# TSOC_CYBLE022.net
KiCad netlist of a schematic drawn in EAGLE
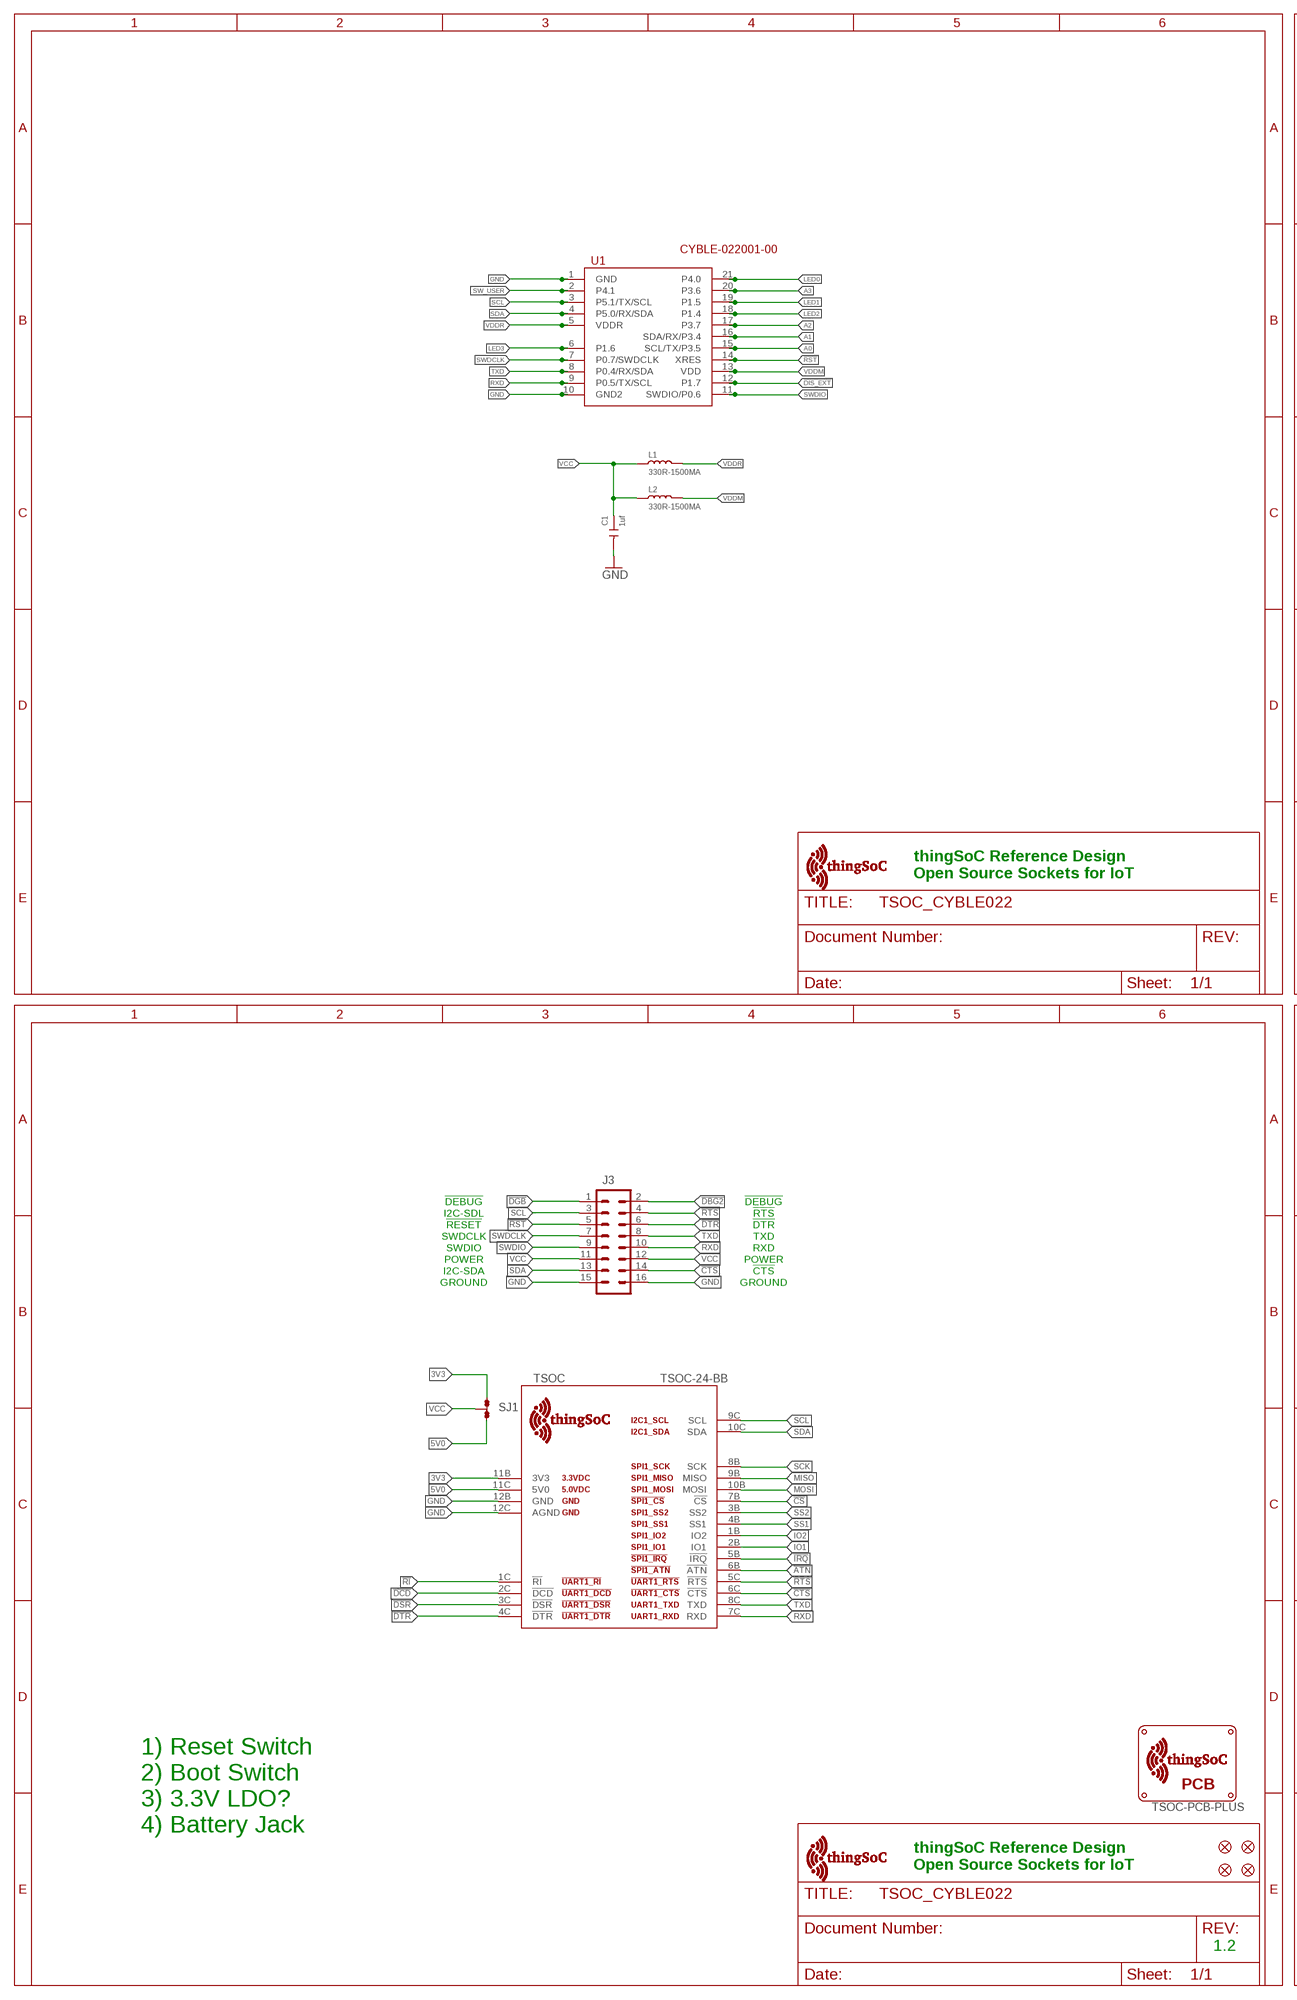
[diagram p0: schematic, sheet 1, part 1 of 2]
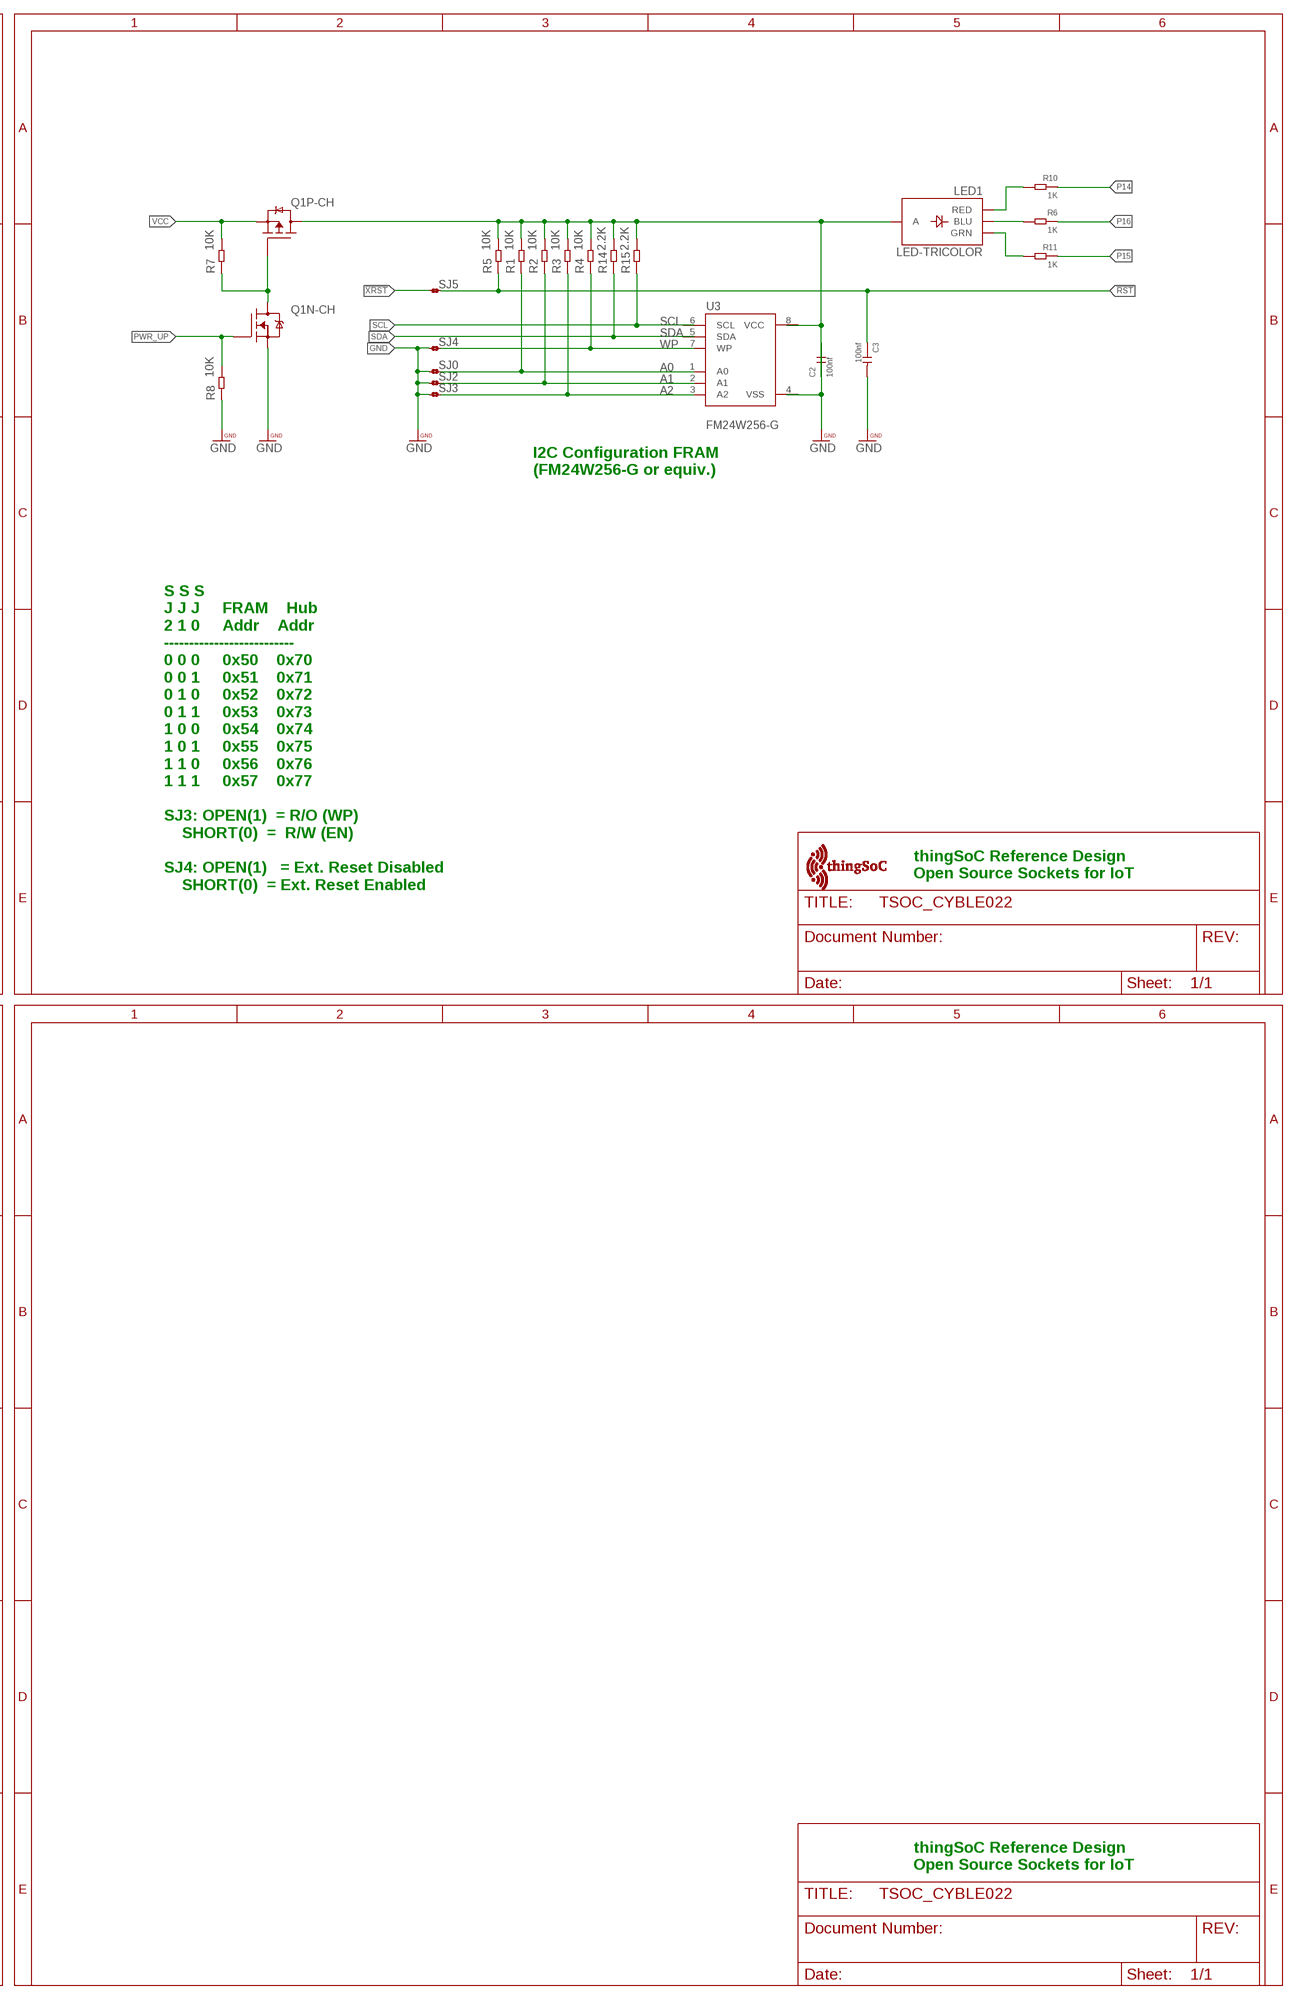
[diagram p1: schematic, sheet 1, part 2 of 2]

(export (version "E")
  (design (tool "Eeschema 10.0.6"))
  (components
    (comp (ref "$$U$4")
      (value "TSOC-LOGO-SMALL")
      (footprint "eagle-import:TSOC-LOGO-SML")
      (libsource (lib "eagle-import") (part "TSOC-LOGO-SMALL"))
    )
    (comp (ref "C1")
      (value "1uf")
      (footprint "eagle-import:C0603")
      (fields (field (name "MPN") "CC0603KRX7R8BB105"))
      (libsource (lib "eagle-import") (part "CERAMIC-1UF-25V-10%-X7R(0603)"))
    )
    (comp (ref "C2")
      (value "100nf")
      (footprint "eagle-import:C0603")
      (fields (field (name "MPN") "CC0603KRX7R9BB104"))
      (libsource (lib "eagle-import") (part "CERAMIC-100NF-50V-10%-X7R(0603)"))
    )
    (comp (ref "C3")
      (value "100nf")
      (footprint "eagle-import:C0603")
      (fields (field (name "MPN") "CC0603KRX7R9BB104"))
      (libsource (lib "eagle-import") (part "CERAMIC-100NF-50V-10%-X7R(0603)"))
    )
    (comp (ref "FID1")
      (value "FIDUCIALUFIDUCIAL")
      (footprint "eagle-import:MICRO-FIDUCIAL")
      (libsource (lib "eagle-import") (part "FIDUCIALUFIDUCIAL"))
    )
    (comp (ref "FID2")
      (value "FIDUCIALUFIDUCIAL")
      (footprint "eagle-import:MICRO-FIDUCIAL")
      (libsource (lib "eagle-import") (part "FIDUCIALUFIDUCIAL"))
    )
    (comp (ref "FID3")
      (value "FIDUCIALUFIDUCIAL")
      (footprint "eagle-import:MICRO-FIDUCIAL")
      (libsource (lib "eagle-import") (part "FIDUCIALUFIDUCIAL"))
    )
    (comp (ref "FID4")
      (value "FIDUCIALUFIDUCIAL")
      (footprint "eagle-import:MICRO-FIDUCIAL")
      (libsource (lib "eagle-import") (part "FIDUCIALUFIDUCIAL"))
    )
    (comp (ref "J3")
      (value "M08X2")
      (footprint "eagle-import:2X8")
      (libsource (lib "eagle-import") (part "M08X2"))
    )
    (comp (ref "L1")
      (value "330R-1500MA")
      (footprint "eagle-import:L0805")
      (fields (field (name "MPN") "BLM21PG331SN1D"))
      (libsource (lib "eagle-import") (part "SMD-FERRITE-BEAD-330R-1500MA(0805)'0805'"))
    )
    (comp (ref "L2")
      (value "330R-1500MA")
      (footprint "eagle-import:L0805")
      (fields (field (name "MPN") "BLM21PG331SN1D"))
      (libsource (lib "eagle-import") (part "SMD-FERRITE-BEAD-330R-1500MA(0805)'0805'"))
    )
    (comp (ref "LED1")
      (value "LED-TRICOLOR")
      (footprint "eagle-import:LED-TRICOLOR-SMD")
      (libsource (lib "eagle-import") (part "LED-TRICOLOR"))
    )
    (comp (ref "Q1")
      (value "FDC6420C")
      (footprint "eagle-import:SOT95P280X110-6N")
      (libsource (lib "eagle-import") (part "FDC6420C"))
    )
    (comp (ref "R1")
      (value "10K")
      (footprint "eagle-import:R0603")
      (fields (field (name "MPN") "RC0603FR-0710KL"))
      (libsource (lib "eagle-import") (part "SMD-RES-10K-1%-1/10W(0603)"))
    )
    (comp (ref "R2")
      (value "10K")
      (footprint "eagle-import:R0603")
      (fields (field (name "MPN") "RC0603FR-0710KL"))
      (libsource (lib "eagle-import") (part "SMD-RES-10K-1%-1/10W(0603)"))
    )
    (comp (ref "R3")
      (value "10K")
      (footprint "eagle-import:R0603")
      (fields (field (name "MPN") "RC0603FR-0710KL"))
      (libsource (lib "eagle-import") (part "SMD-RES-10K-1%-1/10W(0603)"))
    )
    (comp (ref "R4")
      (value "10K")
      (footprint "eagle-import:R0603")
      (fields (field (name "MPN") "RC0603FR-0710KL"))
      (libsource (lib "eagle-import") (part "SMD-RES-10K-1%-1/10W(0603)"))
    )
    (comp (ref "R5")
      (value "10K")
      (footprint "eagle-import:R0603")
      (fields (field (name "MPN") "RC0603FR-0710KL"))
      (libsource (lib "eagle-import") (part "SMD-RES-10K-1%-1/10W(0603)"))
    )
    (comp (ref "R6")
      (value "1K")
      (footprint "eagle-import:R0603")
      (fields (field (name "MPN") "RC0603FR-071KL"))
      (libsource (lib "eagle-import") (part "SMD-RES-1K-1%-1/10W(0603)"))
    )
    (comp (ref "R7")
      (value "10K")
      (footprint "eagle-import:R0603")
      (fields (field (name "MPN") "RC0603FR-0710KL"))
      (libsource (lib "eagle-import") (part "SMD-RES-10K-1%-1/10W(0603)"))
    )
    (comp (ref "R8")
      (value "10K")
      (footprint "eagle-import:R0603")
      (fields (field (name "MPN") "RC0603FR-0710KL"))
      (libsource (lib "eagle-import") (part "SMD-RES-10K-1%-1/10W(0603)"))
    )
    (comp (ref "R10")
      (value "1K")
      (footprint "eagle-import:R0603")
      (fields (field (name "MPN") "RC0603FR-071KL"))
      (libsource (lib "eagle-import") (part "SMD-RES-1K-1%-1/10W(0603)"))
    )
    (comp (ref "R11")
      (value "1K")
      (footprint "eagle-import:R0603")
      (fields (field (name "MPN") "RC0603FR-071KL"))
      (libsource (lib "eagle-import") (part "SMD-RES-1K-1%-1/10W(0603)"))
    )
    (comp (ref "R14")
      (value "2.2K")
      (footprint "eagle-import:R0603")
      (fields (field (name "MPN") "RC0603JR-072K2L"))
      (libsource (lib "eagle-import") (part "SMD-RES-2.2K-5%-1/10W(0603)"))
    )
    (comp (ref "R15")
      (value "2.2K")
      (footprint "eagle-import:R0603")
      (fields (field (name "MPN") "RC0603JR-072K2L"))
      (libsource (lib "eagle-import") (part "SMD-RES-2.2K-5%-1/10W(0603)"))
    )
    (comp (ref "SJ0")
      (value "JMP-2-NO")
      (footprint "eagle-import:JMP-2-NO")
      (libsource (lib "eagle-import") (part "JMP-2-NO"))
    )
    (comp (ref "SJ1")
      (value "JMP-3-NC")
      (footprint "eagle-import:JMP-3-NC")
      (libsource (lib "eagle-import") (part "JMP-3-NC"))
    )
    (comp (ref "SJ2")
      (value "JMP-2-NO")
      (footprint "eagle-import:JMP-2-NO")
      (libsource (lib "eagle-import") (part "JMP-2-NO"))
    )
    (comp (ref "SJ3")
      (value "JMP-2-NO")
      (footprint "eagle-import:JMP-2-NO")
      (libsource (lib "eagle-import") (part "JMP-2-NO"))
    )
    (comp (ref "SJ4")
      (value "JMP-2-NO")
      (footprint "eagle-import:JMP-2-NO")
      (libsource (lib "eagle-import") (part "JMP-2-NO"))
    )
    (comp (ref "SJ5")
      (value "JMP-2-NO")
      (footprint "eagle-import:JMP-2-NO")
      (libsource (lib "eagle-import") (part "JMP-2-NO"))
    )
    (comp (ref "TSOC")
      (value "TSOC-24-BB")
      (footprint "eagle-import:TSOC-BB-S24")
      (libsource (lib "eagle-import") (part "TSOC-24-BB"))
    )
    (comp (ref "U$1")
      (value "TSOC-PCB-PLUS")
      (footprint "eagle-import:TSOC-BB-BRD-PLUS-DIM")
      (libsource (lib "eagle-import") (part "TSOC-PCB-PLUS"))
    )
    (comp (ref "U$100")
      (value "TSOC-LOGO-SMALL")
      (footprint "eagle-import:TSOC-LOGO-SML")
      (libsource (lib "eagle-import") (part "TSOC-LOGO-SMALL"))
    )
    (comp (ref "U$101")
      (value "TSOC-LOGO-LRG")
      (footprint "eagle-import:TSOC-LOGO-LRG")
      (libsource (lib "eagle-import") (part "TSOC-LOGO-LRG"))
    )
    (comp (ref "U1")
      (value "CYBLE-022001-00")
      (footprint "eagle-import:PROC-BLE-10MM-21")
      (libsource (lib "eagle-import") (part "CYBLE-022001-00"))
    )
    (comp (ref "U3")
      (value "FM24W256-G")
      (footprint "eagle-import:SO08")
      (libsource (lib "eagle-import") (part "FM24W256-G"))
    )
  )
  (nets
    (net (code "1") (name "/WP") (class "Default")
      (node (ref "R4") (pin "1") (pinfunction "1_1") (pintype "passive"))
      (node (ref "SJ4") (pin "2") (pinfunction "2_2") (pintype "passive"))
      (node (ref "U3") (pin "7") (pinfunction "WP_7") (pintype "bidirectional"))
    )
    (net (code "2") (name "/~{ATN}") (class "Default")
      (node (ref "TSOC") (pin "6B") (pinfunction "~{ATN}_6B") (pintype "bidirectional"))
    )
    (net (code "3") (name "/~{CS}") (class "Default")
      (node (ref "TSOC") (pin "7B") (pinfunction "~{CS}_7B") (pintype "bidirectional"))
    )
    (net (code "4") (name "/~{CTS}") (class "Default")
      (node (ref "J3") (pin "14") (pinfunction "14_14") (pintype "passive"))
      (node (ref "TSOC") (pin "6C") (pinfunction "~{CTS}_6C") (pintype "bidirectional"))
    )
    (net (code "5") (name "/~{DBG2}") (class "Default")
      (node (ref "J3") (pin "2") (pinfunction "2_2") (pintype "passive"))
    )
    (net (code "6") (name "/~{DCD}") (class "Default")
      (node (ref "TSOC") (pin "2C") (pinfunction "~{DCD}_2C") (pintype "bidirectional"))
    )
    (net (code "7") (name "/~{DGB}") (class "Default")
      (node (ref "J3") (pin "1") (pinfunction "1_1") (pintype "passive"))
    )
    (net (code "8") (name "/~{DIS_EXT}") (class "Default")
      (node (ref "U1") (pin "12") (pinfunction "P1.7_12") (pintype "bidirectional"))
    )
    (net (code "9") (name "/~{DSR}") (class "Default")
      (node (ref "TSOC") (pin "3C") (pinfunction "~{DSR}_3C") (pintype "bidirectional"))
    )
    (net (code "10") (name "/~{DTR}") (class "Default")
      (node (ref "J3") (pin "6") (pinfunction "6_6") (pintype "passive"))
      (node (ref "TSOC") (pin "4C") (pinfunction "~{DTR}_4C") (pintype "bidirectional"))
    )
    (net (code "11") (name "/~{IRQ}") (class "Default")
      (node (ref "TSOC") (pin "5B") (pinfunction "~{IRQ}_5B") (pintype "bidirectional"))
    )
    (net (code "12") (name "/~{RI}") (class "Default")
      (node (ref "TSOC") (pin "1C") (pinfunction "~{RI}_1C") (pintype "bidirectional"))
    )
    (net (code "13") (name "/~{RST}") (class "Default")
      (node (ref "C3") (pin "1") (pinfunction "1_1") (pintype "passive"))
      (node (ref "J3") (pin "5") (pinfunction "5_5") (pintype "passive"))
      (node (ref "R5") (pin "1") (pinfunction "1_1") (pintype "passive"))
      (node (ref "SJ5") (pin "1") (pinfunction "1_1") (pintype "passive"))
      (node (ref "U1") (pin "14") (pinfunction "XRES_14") (pintype "input"))
    )
    (net (code "14") (name "/~{RTS}") (class "Default")
      (node (ref "J3") (pin "4") (pinfunction "4_4") (pintype "passive"))
      (node (ref "TSOC") (pin "5C") (pinfunction "~{RTS}_5C") (pintype "bidirectional"))
    )
    (net (code "15") (name "/~{XRST}") (class "Default")
      (node (ref "SJ5") (pin "2") (pinfunction "2_2") (pintype "passive"))
    )
    (net (code "16") (name "3V3") (class "Default")
      (node (ref "SJ1") (pin "1") (pinfunction "1_1") (pintype "passive"))
      (node (ref "TSOC") (pin "11B") (pinfunction "3V3_11B") (pintype "bidirectional"))
    )
    (net (code "17") (name "5V0") (class "Default")
      (node (ref "SJ1") (pin "3") (pinfunction "3_3") (pintype "passive"))
      (node (ref "TSOC") (pin "11C") (pinfunction "5V0_11C") (pintype "bidirectional"))
    )
    (net (code "18") (name "A0") (class "Default")
      (node (ref "R1") (pin "1") (pinfunction "1_1") (pintype "passive"))
      (node (ref "SJ0") (pin "2") (pinfunction "2_2") (pintype "passive"))
      (node (ref "U1") (pin "15") (pinfunction "SCL/TX/P3.5_15") (pintype "bidirectional"))
      (node (ref "U3") (pin "1") (pinfunction "A0_1") (pintype "bidirectional"))
    )
    (net (code "19") (name "A1") (class "Default")
      (node (ref "R2") (pin "1") (pinfunction "1_1") (pintype "passive"))
      (node (ref "SJ2") (pin "2") (pinfunction "2_2") (pintype "passive"))
      (node (ref "U1") (pin "16") (pinfunction "SDA/RX/P3.4_16") (pintype "bidirectional"))
      (node (ref "U3") (pin "2") (pinfunction "A1_2") (pintype "bidirectional"))
    )
    (net (code "20") (name "A2") (class "Default")
      (node (ref "R3") (pin "1") (pinfunction "1_1") (pintype "passive"))
      (node (ref "SJ3") (pin "2") (pinfunction "2_2") (pintype "passive"))
      (node (ref "U1") (pin "17") (pinfunction "P3.7_17") (pintype "bidirectional"))
      (node (ref "U3") (pin "3") (pinfunction "A2_3") (pintype "bidirectional"))
    )
    (net (code "21") (name "A3") (class "Default")
      (node (ref "U1") (pin "20") (pinfunction "P3.6_20") (pintype "bidirectional"))
    )
    (net (code "22") (name "GND") (class "Default")
      (node (ref "C1") (pin "2") (pinfunction "2_2") (pintype "passive"))
      (node (ref "C2") (pin "2") (pinfunction "2_2") (pintype "passive"))
      (node (ref "C3") (pin "2") (pinfunction "2_2") (pintype "passive"))
      (node (ref "J3") (pin "15") (pinfunction "15_15") (pintype "passive"))
      (node (ref "J3") (pin "16") (pinfunction "16_16") (pintype "passive"))
      (node (ref "Q1") (pin "5") (pinfunction "S_5") (pintype "passive"))
      (node (ref "R8") (pin "1") (pinfunction "1_1") (pintype "passive"))
      (node (ref "SJ0") (pin "1") (pinfunction "1_1") (pintype "passive"))
      (node (ref "SJ2") (pin "1") (pinfunction "1_1") (pintype "passive"))
      (node (ref "SJ3") (pin "1") (pinfunction "1_1") (pintype "passive"))
      (node (ref "SJ4") (pin "1") (pinfunction "1_1") (pintype "passive"))
      (node (ref "TSOC") (pin "12B") (pinfunction "GND_12B") (pintype "bidirectional"))
      (node (ref "TSOC") (pin "12C") (pinfunction "AGND_12C") (pintype "bidirectional"))
      (node (ref "U1") (pin "1") (pinfunction "GND_1") (pintype "power_in"))
      (node (ref "U1") (pin "10") (pinfunction "GND2_10") (pintype "power_in"))
      (node (ref "U3") (pin "4") (pinfunction "VSS_4") (pintype "power_in"))
    )
    (net (code "23") (name "IO1") (class "Default")
      (node (ref "TSOC") (pin "2B") (pinfunction "IO1_2B") (pintype "bidirectional"))
    )
    (net (code "24") (name "IO2") (class "Default")
      (node (ref "TSOC") (pin "1B") (pinfunction "IO2_1B") (pintype "bidirectional"))
    )
    (net (code "25") (name "LED0") (class "Default")
      (node (ref "U1") (pin "21") (pinfunction "P4.0_21") (pintype "bidirectional"))
    )
    (net (code "26") (name "LED1") (class "Default")
      (node (ref "U1") (pin "19") (pinfunction "P1.5_19") (pintype "bidirectional"))
    )
    (net (code "27") (name "LED2") (class "Default")
      (node (ref "U1") (pin "18") (pinfunction "P1.4_18") (pintype "bidirectional"))
    )
    (net (code "28") (name "LED3") (class "Default")
      (node (ref "U1") (pin "6") (pinfunction "P1.6_6") (pintype "bidirectional"))
    )
    (net (code "29") (name "MISO") (class "Default")
      (node (ref "TSOC") (pin "9B") (pinfunction "MISO_9B") (pintype "bidirectional"))
    )
    (net (code "30") (name "MOSI") (class "Default")
      (node (ref "TSOC") (pin "10B") (pinfunction "MOSI_10B") (pintype "bidirectional"))
    )
    (net (code "31") (name "Net-(LED1-BLU)") (class "Default")
      (node (ref "LED1") (pin "B") (pinfunction "BLU_B") (pintype "bidirectional"))
      (node (ref "R6") (pin "2") (pinfunction "2_2") (pintype "passive"))
    )
    (net (code "32") (name "Net-(LED1-GRN)") (class "Default")
      (node (ref "LED1") (pin "G") (pinfunction "GRN_G") (pintype "bidirectional"))
      (node (ref "R11") (pin "2") (pinfunction "2_2") (pintype "passive"))
    )
    (net (code "33") (name "Net-(LED1-RED)") (class "Default")
      (node (ref "LED1") (pin "R") (pinfunction "RED_R") (pintype "bidirectional"))
      (node (ref "R10") (pin "2") (pinfunction "2_2") (pintype "passive"))
    )
    (net (code "34") (name "Net-(Q1A-D)") (class "Default")
      (node (ref "Q1") (pin "3") (pinfunction "G_3") (pintype "passive"))
      (node (ref "Q1") (pin "6") (pinfunction "D_6") (pintype "passive"))
      (node (ref "R7") (pin "1") (pinfunction "1_1") (pintype "passive"))
    )
    (net (code "35") (name "Net-(Q1B-D)") (class "Default")
      (node (ref "C2") (pin "1") (pinfunction "1_1") (pintype "passive"))
      (node (ref "LED1") (pin "A") (pinfunction "A_A") (pintype "bidirectional"))
      (node (ref "Q1") (pin "4") (pinfunction "D_4") (pintype "passive"))
      (node (ref "R1") (pin "2") (pinfunction "2_2") (pintype "passive"))
      (node (ref "R14") (pin "2") (pinfunction "2_2") (pintype "passive"))
      (node (ref "R15") (pin "2") (pinfunction "2_2") (pintype "passive"))
      (node (ref "R2") (pin "2") (pinfunction "2_2") (pintype "passive"))
      (node (ref "R3") (pin "2") (pinfunction "2_2") (pintype "passive"))
      (node (ref "R4") (pin "2") (pinfunction "2_2") (pintype "passive"))
      (node (ref "R5") (pin "2") (pinfunction "2_2") (pintype "passive"))
      (node (ref "U3") (pin "8") (pinfunction "VCC_8") (pintype "power_in"))
    )
    (net (code "36") (name "P14") (class "Default")
      (node (ref "R10") (pin "1") (pinfunction "1_1") (pintype "passive"))
    )
    (net (code "37") (name "P15") (class "Default")
      (node (ref "R11") (pin "1") (pinfunction "1_1") (pintype "passive"))
    )
    (net (code "38") (name "P16") (class "Default")
      (node (ref "R6") (pin "1") (pinfunction "1_1") (pintype "passive"))
    )
    (net (code "39") (name "PWR_UP") (class "Default")
      (node (ref "Q1") (pin "1") (pinfunction "G_1") (pintype "passive"))
      (node (ref "R8") (pin "2") (pinfunction "2_2") (pintype "passive"))
    )
    (net (code "40") (name "RXD") (class "Default")
      (node (ref "J3") (pin "10") (pinfunction "10_10") (pintype "passive"))
      (node (ref "TSOC") (pin "7C") (pinfunction "RXD_7C") (pintype "bidirectional"))
      (node (ref "U1") (pin "9") (pinfunction "P0.5/TX/SCL_9") (pintype "bidirectional"))
    )
    (net (code "41") (name "SCK") (class "Default")
      (node (ref "TSOC") (pin "8B") (pinfunction "SCK_8B") (pintype "bidirectional"))
    )
    (net (code "42") (name "SCL") (class "Default")
      (node (ref "J3") (pin "3") (pinfunction "3_3") (pintype "passive"))
      (node (ref "R15") (pin "1") (pinfunction "1_1") (pintype "passive"))
      (node (ref "TSOC") (pin "9C") (pinfunction "SCL_9C") (pintype "bidirectional"))
      (node (ref "U1") (pin "3") (pinfunction "P5.1/TX/SCL_3") (pintype "bidirectional"))
      (node (ref "U3") (pin "6") (pinfunction "SCL_6") (pintype "bidirectional"))
    )
    (net (code "43") (name "SDA") (class "Default")
      (node (ref "J3") (pin "13") (pinfunction "13_13") (pintype "passive"))
      (node (ref "R14") (pin "1") (pinfunction "1_1") (pintype "passive"))
      (node (ref "TSOC") (pin "10C") (pinfunction "SDA_10C") (pintype "bidirectional"))
      (node (ref "U1") (pin "4") (pinfunction "P5.0/RX/SDA_4") (pintype "bidirectional"))
      (node (ref "U3") (pin "5") (pinfunction "SDA_5") (pintype "bidirectional"))
    )
    (net (code "44") (name "SS1") (class "Default")
      (node (ref "TSOC") (pin "4B") (pinfunction "SS1_4B") (pintype "bidirectional"))
    )
    (net (code "45") (name "SS2") (class "Default")
      (node (ref "TSOC") (pin "3B") (pinfunction "SS2_3B") (pintype "bidirectional"))
    )
    (net (code "46") (name "SWDCLK") (class "Default")
      (node (ref "J3") (pin "7") (pinfunction "7_7") (pintype "passive"))
      (node (ref "U1") (pin "7") (pinfunction "P0.7/SWDCLK_7") (pintype "bidirectional"))
    )
    (net (code "47") (name "SWDIO") (class "Default")
      (node (ref "J3") (pin "9") (pinfunction "9_9") (pintype "passive"))
      (node (ref "U1") (pin "11") (pinfunction "SWDIO/P0.6_11") (pintype "bidirectional"))
    )
    (net (code "48") (name "SW_USER") (class "Default")
      (node (ref "U1") (pin "2") (pinfunction "P4.1_2") (pintype "bidirectional"))
    )
    (net (code "49") (name "TXD") (class "Default")
      (node (ref "J3") (pin "8") (pinfunction "8_8") (pintype "passive"))
      (node (ref "TSOC") (pin "8C") (pinfunction "TXD_8C") (pintype "bidirectional"))
      (node (ref "U1") (pin "8") (pinfunction "P0.4/RX/SDA_8") (pintype "bidirectional"))
    )
    (net (code "50") (name "VCC") (class "Default")
      (node (ref "C1") (pin "1") (pinfunction "1_1") (pintype "passive"))
      (node (ref "J3") (pin "11") (pinfunction "11_11") (pintype "passive"))
      (node (ref "J3") (pin "12") (pinfunction "12_12") (pintype "passive"))
      (node (ref "L1") (pin "1") (pinfunction "1_1") (pintype "passive"))
      (node (ref "L2") (pin "1") (pinfunction "1_1") (pintype "passive"))
      (node (ref "Q1") (pin "2") (pinfunction "S_2") (pintype "passive"))
      (node (ref "R7") (pin "2") (pinfunction "2_2") (pintype "passive"))
      (node (ref "SJ1") (pin "2") (pinfunction "2_2") (pintype "passive"))
    )
    (net (code "51") (name "VDDM") (class "Default")
      (node (ref "L2") (pin "2") (pinfunction "2_2") (pintype "passive"))
      (node (ref "U1") (pin "13") (pinfunction "VDD_13") (pintype "power_in"))
    )
    (net (code "52") (name "VDDR") (class "Default")
      (node (ref "L1") (pin "2") (pinfunction "2_2") (pintype "passive"))
      (node (ref "U1") (pin "5") (pinfunction "VDDR_5") (pintype "power_in"))
    )
  )
)
